# midi_in.net
KiCad netlist of a schematic drawn in EAGLE
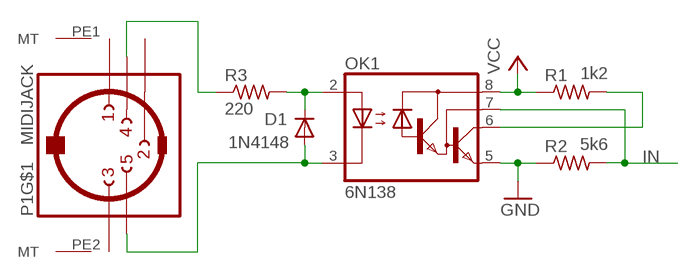
[diagram p0: schematic, sheet 1]

(export (version "E")
  (design (tool "Eeschema 10.0.6"))
  (components
    (comp (ref "D1")
      (value "1N4148")
      (footprint "eagle-import:DO35-7")
      (libsource (lib "eagle-import") (part "1N4148DO35-7"))
    )
    (comp (ref "OK1")
      (value "6N138")
      (footprint "eagle-import:DIL08")
      (fields (field (name "MF") "VISHAY/TELEFUNKEN"))
      (libsource (lib "eagle-import") (part "6N138"))
    )
    (comp (ref "P1")
      (value "MIDIJACK")
      (footprint "eagle-import:CP-2350")
      (libsource (lib "eagle-import") (part "MIDIJACK"))
    )
    (comp (ref "R1")
      (value "1k2")
      (footprint "eagle-import:0204_5")
      (libsource (lib "eagle-import") (part "R-US_0204/5"))
    )
    (comp (ref "R2")
      (value "5k6")
      (footprint "eagle-import:0204_5")
      (libsource (lib "eagle-import") (part "R-US_0204/5"))
    )
    (comp (ref "R3")
      (value "220")
      (footprint "eagle-import:0204_5")
      (libsource (lib "eagle-import") (part "R-US_0204/5"))
    )
  )
  (nets
    (net (code "1") (name "/IN") (class "Default")
      (node (ref "OK1") (pin "7") (pinfunction "VB_7") (pintype "passive"))
      (node (ref "R2") (pin "2") (pinfunction "2_2") (pintype "passive"))
    )
    (net (code "2") (name "GND") (class "Default")
      (node (ref "OK1") (pin "5") (pinfunction "GND_5") (pintype "passive"))
      (node (ref "R2") (pin "1") (pinfunction "1_1") (pintype "passive"))
    )
    (net (code "3") (name "Net-(OK1-A)") (class "Default")
      (node (ref "D1") (pin "C") (pinfunction "C_C") (pintype "passive"))
      (node (ref "OK1") (pin "2") (pinfunction "A_2") (pintype "passive"))
      (node (ref "R3") (pin "2") (pinfunction "2_2") (pintype "passive"))
    )
    (net (code "4") (name "Net-(OK1-C)") (class "Default")
      (node (ref "D1") (pin "A") (pinfunction "A_A") (pintype "passive"))
      (node (ref "OK1") (pin "3") (pinfunction "C_3") (pintype "passive"))
      (node (ref "P1") (pin "5") (pinfunction "5_5") (pintype "passive"))
    )
    (net (code "5") (name "Net-(OK1-VO)") (class "Default")
      (node (ref "OK1") (pin "6") (pinfunction "VO_6") (pintype "passive"))
      (node (ref "R1") (pin "2") (pinfunction "2_2") (pintype "passive"))
    )
    (net (code "6") (name "Net-(P1-Pad4)") (class "Default")
      (node (ref "P1") (pin "4") (pinfunction "4_4") (pintype "passive"))
      (node (ref "R3") (pin "1") (pinfunction "1_1") (pintype "passive"))
    )
    (net (code "7") (name "VCC") (class "Default")
      (node (ref "OK1") (pin "8") (pinfunction "VCC_8") (pintype "passive"))
      (node (ref "R1") (pin "1") (pinfunction "1_1") (pintype "passive"))
    )
    (net (code "8") (name "unconnected-(P1-Pad1)") (class "Default")
      (node (ref "P1") (pin "1") (pinfunction "1_1") (pintype "passive"))
    )
    (net (code "9") (name "unconnected-(P1-Pad2)") (class "Default")
      (node (ref "P1") (pin "2") (pinfunction "2_2") (pintype "passive"))
    )
    (net (code "10") (name "unconnected-(P1-Pad3)") (class "Default")
      (node (ref "P1") (pin "3") (pinfunction "3_3") (pintype "passive"))
    )
    (net (code "11") (name "unconnected-(P1D-MT-PadPE1)") (class "Default")
      (node (ref "P1") (pin "PE1") (pinfunction "MT_PE1") (pintype "passive"))
    )
    (net (code "12") (name "unconnected-(P1E-MT-PadPE2)") (class "Default")
      (node (ref "P1") (pin "PE2") (pinfunction "MT_PE2") (pintype "passive"))
    )
  )
)
